# untitled.net
KiCad netlist of a schematic drawn in EAGLE
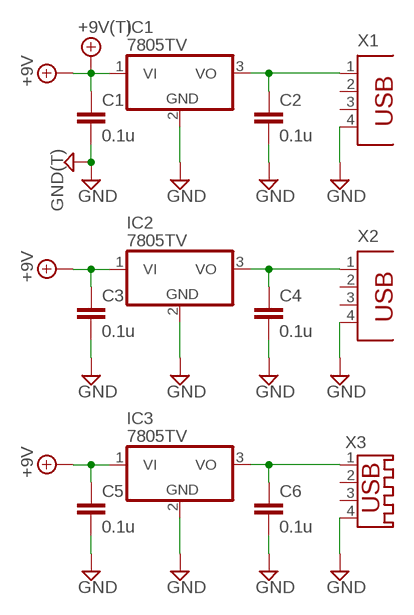
[diagram p0: schematic, sheet 1]

(export (version "E")
  (design (tool "Eeschema 10.0.6"))
  (components
    (comp (ref "+9V1")
      (value "+9V(T)")
      (footprint "eagle-import:SQUARE")
      (libsource (lib "eagle-import") (part "+9V(T)"))
    )
    (comp (ref "C1")
      (value "0.1u")
      (footprint "eagle-import:075X035_4")
      (libsource (lib "eagle-import") (part "075X0354"))
    )
    (comp (ref "C2")
      (value "0.1u")
      (footprint "eagle-import:075X035_4")
      (libsource (lib "eagle-import") (part "075X0354"))
    )
    (comp (ref "C3")
      (value "0.1u")
      (footprint "eagle-import:075X035_4")
      (libsource (lib "eagle-import") (part "075X0354"))
    )
    (comp (ref "C4")
      (value "0.1u")
      (footprint "eagle-import:075X035_4")
      (libsource (lib "eagle-import") (part "075X0354"))
    )
    (comp (ref "C5")
      (value "0.1u")
      (footprint "eagle-import:075X035_4")
      (libsource (lib "eagle-import") (part "075X0354"))
    )
    (comp (ref "C6")
      (value "0.1u")
      (footprint "eagle-import:075X035_4")
      (libsource (lib "eagle-import") (part "075X0354"))
    )
    (comp (ref "GND1")
      (value "GND(T)")
      (footprint "eagle-import:SQUARE")
      (libsource (lib "eagle-import") (part "GND(T)"))
    )
    (comp (ref "IC1")
      (value "7805TV")
      (footprint "eagle-import:TO220V")
      (libsource (lib "eagle-import") (part "78TV05"))
    )
    (comp (ref "IC2")
      (value "7805TV")
      (footprint "eagle-import:TO220V")
      (libsource (lib "eagle-import") (part "78TV05"))
    )
    (comp (ref "IC3")
      (value "7805TV")
      (footprint "eagle-import:TO220V")
      (libsource (lib "eagle-import") (part "78TV05"))
    )
    (comp (ref "X1")
      (value "PN87520")
      (footprint "eagle-import:PN87520")
      (libsource (lib "eagle-import") (part "PN87520"))
    )
    (comp (ref "X2")
      (value "PN87520")
      (footprint "eagle-import:PN87520")
      (libsource (lib "eagle-import") (part "PN87520"))
    )
    (comp (ref "X3")
      (value "USB-A003")
      (footprint "eagle-import:USB-A003")
      (libsource (lib "eagle-import") (part "USB-A003"))
    )
  )
  (nets
    (net (code "1") (name "+9V") (class "Default")
      (node (ref "+9V1") (pin "1") (pinfunction "+9V_1") (pintype "power_in"))
      (node (ref "C1") (pin "1") (pinfunction "1_1") (pintype "passive"))
      (node (ref "C3") (pin "1") (pinfunction "1_1") (pintype "passive"))
      (node (ref "C5") (pin "1") (pinfunction "1_1") (pintype "passive"))
      (node (ref "IC1") (pin "1") (pinfunction "VI_1") (pintype "input"))
      (node (ref "IC2") (pin "1") (pinfunction "VI_1") (pintype "input"))
      (node (ref "IC3") (pin "1") (pinfunction "VI_1") (pintype "input"))
    )
    (net (code "2") (name "GND") (class "Default")
      (node (ref "C1") (pin "2") (pinfunction "2_2") (pintype "passive"))
      (node (ref "C2") (pin "2") (pinfunction "2_2") (pintype "passive"))
      (node (ref "C3") (pin "2") (pinfunction "2_2") (pintype "passive"))
      (node (ref "C4") (pin "2") (pinfunction "2_2") (pintype "passive"))
      (node (ref "C5") (pin "2") (pinfunction "2_2") (pintype "passive"))
      (node (ref "C6") (pin "2") (pinfunction "2_2") (pintype "passive"))
      (node (ref "GND1") (pin "1") (pinfunction "GND_1") (pintype "power_in"))
      (node (ref "IC1") (pin "2") (pinfunction "GND_2") (pintype "passive"))
      (node (ref "IC2") (pin "2") (pinfunction "GND_2") (pintype "passive"))
      (node (ref "IC3") (pin "2") (pinfunction "GND_2") (pintype "passive"))
      (node (ref "X1") (pin "4") (pinfunction "4_4") (pintype "passive"))
      (node (ref "X2") (pin "4") (pinfunction "4_4") (pintype "passive"))
      (node (ref "X3") (pin "4") (pinfunction "4_4") (pintype "passive"))
    )
    (net (code "3") (name "Net-(IC1-VO)") (class "Default")
      (node (ref "C2") (pin "1") (pinfunction "1_1") (pintype "passive"))
      (node (ref "IC1") (pin "3") (pinfunction "VO_3") (pintype "passive"))
      (node (ref "X1") (pin "1") (pinfunction "1_1") (pintype "passive"))
    )
    (net (code "4") (name "Net-(IC2-VO)") (class "Default")
      (node (ref "C4") (pin "1") (pinfunction "1_1") (pintype "passive"))
      (node (ref "IC2") (pin "3") (pinfunction "VO_3") (pintype "passive"))
      (node (ref "X2") (pin "1") (pinfunction "1_1") (pintype "passive"))
    )
    (net (code "5") (name "Net-(IC3-VO)") (class "Default")
      (node (ref "C6") (pin "1") (pinfunction "1_1") (pintype "passive"))
      (node (ref "IC3") (pin "3") (pinfunction "VO_3") (pintype "passive"))
      (node (ref "X3") (pin "1") (pinfunction "1_1") (pintype "passive"))
    )
    (net (code "6") (name "unconnected-(X1-Pad2)") (class "Default")
      (node (ref "X1") (pin "2") (pinfunction "2_2") (pintype "passive"))
    )
    (net (code "7") (name "unconnected-(X1-Pad3)") (class "Default")
      (node (ref "X1") (pin "3") (pinfunction "3_3") (pintype "passive"))
    )
    (net (code "8") (name "unconnected-(X2-Pad2)") (class "Default")
      (node (ref "X2") (pin "2") (pinfunction "2_2") (pintype "passive"))
    )
    (net (code "9") (name "unconnected-(X2-Pad3)") (class "Default")
      (node (ref "X2") (pin "3") (pinfunction "3_3") (pintype "passive"))
    )
    (net (code "10") (name "unconnected-(X3-Pad2)") (class "Default")
      (node (ref "X3") (pin "2") (pinfunction "2_2") (pintype "passive"))
    )
    (net (code "11") (name "unconnected-(X3-Pad3)") (class "Default")
      (node (ref "X3") (pin "3") (pinfunction "3_3") (pintype "passive"))
    )
  )
)
